# WGPIB.net
KiCad netlist of a schematic drawn in Altium Designer
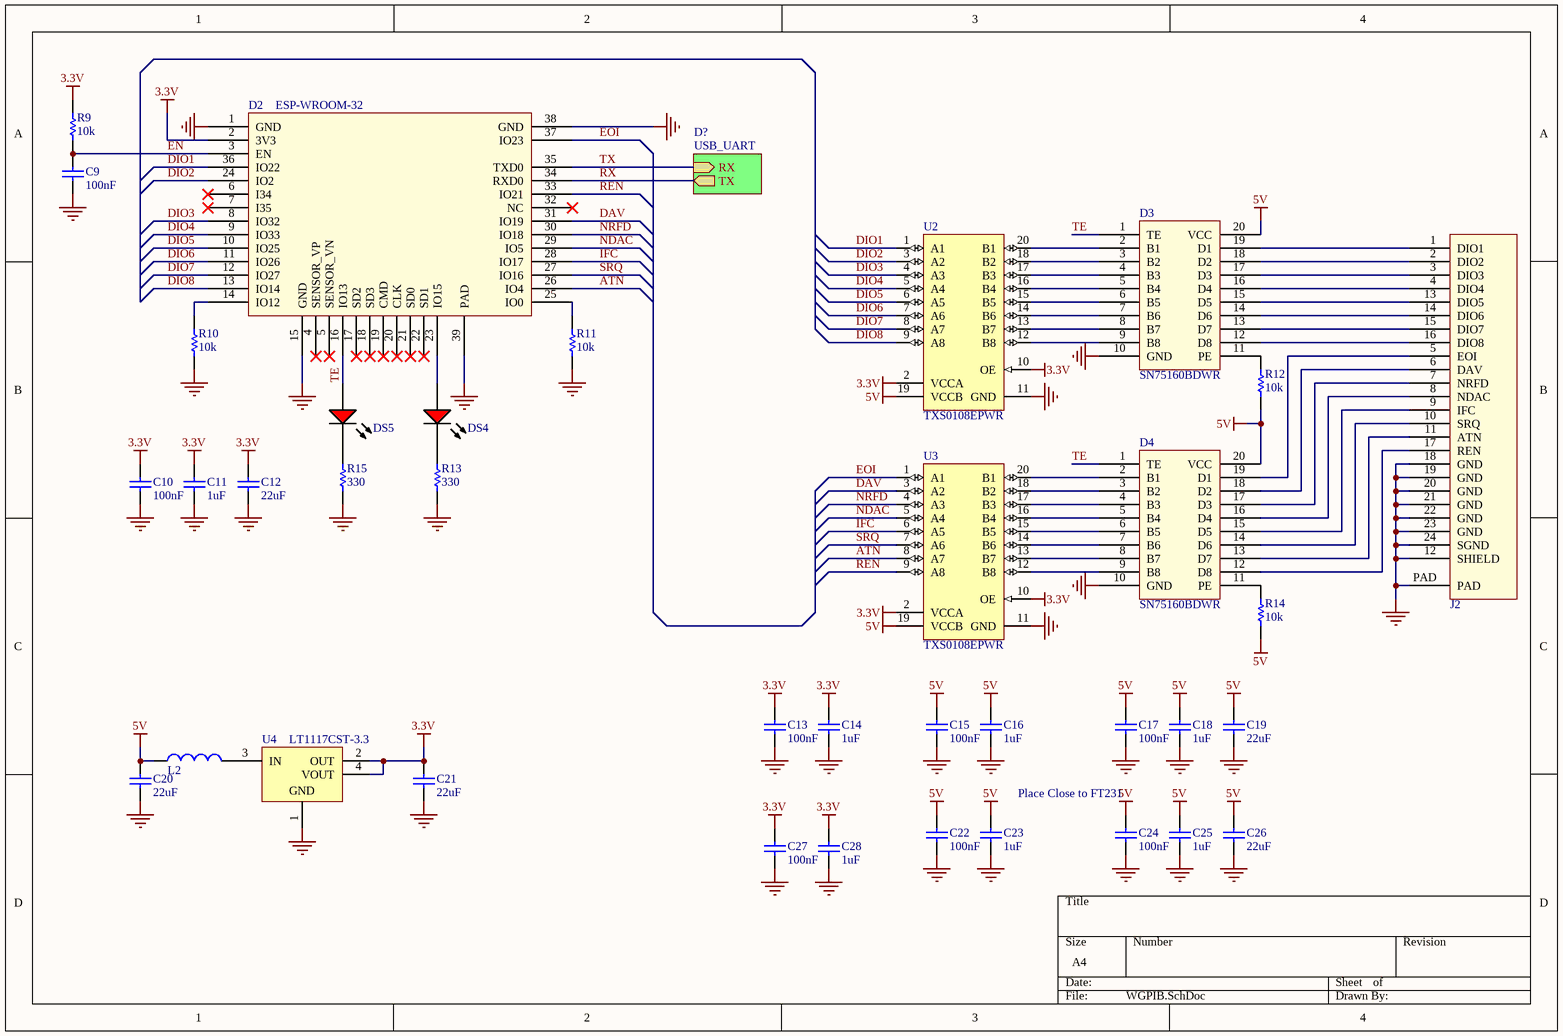
[diagram p0: WGPIB.SchDoc]

(export (version "E")
  (design (tool "Eeschema 10.0.6"))
  (components
    (comp (ref "C9")
      (value "100nF")
      (footprint "CAPC0805(2012)145_N")
      (fields (field (name "TOLERANCE") "Â±20%"))
      (libsource (lib "Altium Content Vault") (part "CAP"))
    )
    (comp (ref "C10")
      (value "100nF")
      (footprint "CAPC0805(2012)145_N")
      (fields (field (name "TOLERANCE") "Â±20%"))
      (libsource (lib "Altium Content Vault") (part "CAP"))
    )
    (comp (ref "C11")
      (value "1uF")
      (footprint "CAPC0805(2012)145_N")
      (fields (field (name "TOLERANCE") "Â±20%"))
      (libsource (lib "Altium Content Vault") (part "CAP"))
    )
    (comp (ref "C12")
      (value "22uF")
      (footprint "CAPC1206(3216)190_M")
      (fields (field (name "TOLERANCE") "Â±20%"))
      (libsource (lib "Altium Content Vault") (part "CAP"))
    )
    (comp (ref "C13")
      (value "100nF")
      (footprint "CAPC0805(2012)145_N")
      (fields (field (name "TOLERANCE") "Â±20%"))
      (libsource (lib "Altium Content Vault") (part "CAP"))
    )
    (comp (ref "C14")
      (value "1uF")
      (footprint "CAPC0805(2012)145_N")
      (fields (field (name "TOLERANCE") "Â±20%"))
      (libsource (lib "Altium Content Vault") (part "CAP"))
    )
    (comp (ref "C15")
      (value "100nF")
      (footprint "CAPC0805(2012)145_N")
      (fields (field (name "TOLERANCE") "Â±20%"))
      (libsource (lib "Altium Content Vault") (part "CAP"))
    )
    (comp (ref "C16")
      (value "1uF")
      (footprint "CAPC0805(2012)145_N")
      (fields (field (name "TOLERANCE") "Â±20%"))
      (libsource (lib "Altium Content Vault") (part "CAP"))
    )
    (comp (ref "C17")
      (value "100nF")
      (footprint "CAPC0805(2012)145_N")
      (fields (field (name "TOLERANCE") "Â±20%"))
      (libsource (lib "Altium Content Vault") (part "CAP"))
    )
    (comp (ref "C18")
      (value "1uF")
      (footprint "CAPC0805(2012)145_N")
      (fields (field (name "TOLERANCE") "Â±20%"))
      (libsource (lib "Altium Content Vault") (part "CAP"))
    )
    (comp (ref "C19")
      (value "22uF")
      (footprint "CAPC1206(3216)190_M")
      (fields (field (name "TOLERANCE") "Â±20%"))
      (libsource (lib "Altium Content Vault") (part "CAP"))
    )
    (comp (ref "C20")
      (value "22uF")
      (footprint "CAPC1206(3216)190_M")
      (fields (field (name "TOLERANCE") "Â±20%"))
      (libsource (lib "Altium Content Vault") (part "CAP"))
    )
    (comp (ref "C21")
      (value "22uF")
      (footprint "CAPC1206(3216)190_M")
      (fields (field (name "TOLERANCE") "Â±20%"))
      (libsource (lib "Altium Content Vault") (part "CAP"))
    )
    (comp (ref "C22")
      (value "100nF")
      (footprint "CAPC0805(2012)145_N")
      (fields (field (name "TOLERANCE") "Â±20%"))
      (libsource (lib "Altium Content Vault") (part "CAP"))
    )
    (comp (ref "C23")
      (value "1uF")
      (footprint "CAPC0805(2012)145_N")
      (fields (field (name "TOLERANCE") "Â±20%"))
      (libsource (lib "Altium Content Vault") (part "CAP"))
    )
    (comp (ref "C24")
      (value "100nF")
      (footprint "CAPC0805(2012)145_N")
      (fields (field (name "TOLERANCE") "Â±20%"))
      (libsource (lib "Altium Content Vault") (part "CAP"))
    )
    (comp (ref "C25")
      (value "1uF")
      (footprint "CAPC0805(2012)145_N")
      (fields (field (name "TOLERANCE") "Â±20%"))
      (libsource (lib "Altium Content Vault") (part "CAP"))
    )
    (comp (ref "C26")
      (value "22uF")
      (footprint "CAPC1206(3216)190_M")
      (fields (field (name "TOLERANCE") "Â±20%"))
      (libsource (lib "Altium Content Vault") (part "CAP"))
    )
    (comp (ref "C27")
      (value "100nF")
      (footprint "CAPC0805(2012)145_N")
      (fields (field (name "TOLERANCE") "Â±20%"))
      (libsource (lib "Altium Content Vault") (part "CAP"))
    )
    (comp (ref "C28")
      (value "1uF")
      (footprint "CAPC0805(2012)145_N")
      (fields (field (name "TOLERANCE") "Â±20%"))
      (libsource (lib "Altium Content Vault") (part "CAP"))
    )
    (comp (ref "D2")
      (value "ESP-WROOM-32")
      (footprint "ESP-WROOM-32")
      (description "ESP32 Module")
      (libsource (lib "DEV_Modules") (part "ESP-WROOM-32"))
    )
    (comp (ref "D3")
      (value "SN75160BDWR")
      (footprint "SOIC-20")
      (libsource (lib "LineDrivers") (part "SN75160BDWR"))
    )
    (comp (ref "D4")
      (value "SN75160BDWR")
      (footprint "SOIC-20")
      (libsource (lib "LineDrivers") (part "SN75160BDWR"))
    )
    (comp (ref "DS4")
      (value "TLMS1100-GS08")
      (footprint "VISH-TLMX1100_V")
      (description "LED, RED, 2.1 V, -40 to 100 degC, 2-Pin SMD (0603), RoHS, Tape and Reel")
      (fields (field (name "TOLERANCE") "5%"))
      (libsource (lib "Altium Content Vault") (part "LED-RED-AK-2"))
    )
    (comp (ref "DS5")
      (value "TLMS1100-GS08")
      (footprint "VISH-TLMX1100_V")
      (description "LED, RED, 2.1 V, -40 to 100 degC, 2-Pin SMD (0603), RoHS, Tape and Reel")
      (fields (field (name "TOLERANCE") "5%"))
      (libsource (lib "Altium Content Vault") (part "LED-RED-AK-2"))
    )
    (comp (ref "J2")
      (value "GPIB")
      (footprint "GPIB THT")
      (description "112-024-113R001")
      (libsource (lib "DSUB_Connector") (part "GPIB"))
    )
    (comp (ref "L2")
      (value "FBMJ2125HM210NT")
      (footprint "INDC2013X105X50LL20T30")
      (description "Chip Inductor, 21 Ohm, +/- 30%, 6 A, -40 to 125 degC, 0805 (2012 Metric), RoHS, Tape and Reel")
      (fields (field (name "TOLERANCE") "30%"))
      (libsource (lib "Altium Content Vault") (part "IND-2"))
    )
    (comp (ref "R9")
      (value "10k")
      (footprint "RESC0805(2012)_M")
      (fields (field (name "POWER") "0.125 W") (field (name "TOLERANCE") "5 %"))
      (libsource (lib "Altium Content Vault") (part "RES"))
    )
    (comp (ref "R10")
      (value "10k")
      (footprint "RESC0805(2012)_M")
      (fields (field (name "POWER") "0.125 W") (field (name "TOLERANCE") "5 %"))
      (libsource (lib "Altium Content Vault") (part "RES"))
    )
    (comp (ref "R11")
      (value "10k")
      (footprint "RESC0805(2012)_M")
      (fields (field (name "POWER") "0.125 W") (field (name "TOLERANCE") "5 %"))
      (libsource (lib "Altium Content Vault") (part "RES"))
    )
    (comp (ref "R12")
      (value "10k")
      (footprint "RESC0805(2012)_M")
      (fields (field (name "POWER") "0.125 W") (field (name "TOLERANCE") "5 %"))
      (libsource (lib "Altium Content Vault") (part "RES"))
    )
    (comp (ref "R13")
      (value "330")
      (footprint "RESC0805(2012)_M")
      (fields (field (name "POWER") "0.125 W") (field (name "TOLERANCE") "5 %"))
      (libsource (lib "Altium Content Vault") (part "RES"))
    )
    (comp (ref "R14")
      (value "10k")
      (footprint "RESC0805(2012)_M")
      (fields (field (name "POWER") "0.125 W") (field (name "TOLERANCE") "5 %"))
      (libsource (lib "Altium Content Vault") (part "RES"))
    )
    (comp (ref "R15")
      (value "330")
      (footprint "RESC0805(2012)_M")
      (fields (field (name "POWER") "0.125 W") (field (name "TOLERANCE") "5 %"))
      (libsource (lib "Altium Content Vault") (part "RES"))
    )
    (comp (ref "U2")
      (value "TXS0108EPWR")
      (footprint "PW0020A_M")
      (fields (field (name "MANUFACTURER") "Texas Instruments"))
      (libsource (lib "Altium Content Vault") (part "TI-TXS0108EPWR-SOP-20"))
    )
    (comp (ref "U3")
      (value "TXS0108EPWR")
      (footprint "PW0020A_M")
      (fields (field (name "MANUFACTURER") "Texas Instruments"))
      (libsource (lib "Altium Content Vault") (part "TI-TXS0108EPWR-SOP-20"))
    )
    (comp (ref "U4")
      (value "LT1117CST-3.3")
      (footprint "LT-ST-3-SOT-223_M")
      (fields (field (name "MANUFACTURER") "Linear Technology"))
      (libsource (lib "Altium Content Vault") (part "LT-LT1117-3_B"))
    )
  )
  (nets
    (net (code "1") (name "/ATN") (class "Default")
      (node (ref "D2") (pin "26") (pinfunction "IO4_26") (pintype "passive"))
      (node (ref "U3") (pin "8") (pinfunction "A7_8") (pintype "bidirectional"))
    )
    (net (code "2") (name "/DAV") (class "Default")
      (node (ref "D2") (pin "31") (pinfunction "IO19_31") (pintype "passive"))
      (node (ref "U3") (pin "3") (pinfunction "A2_3") (pintype "bidirectional"))
    )
    (net (code "3") (name "/DIO1") (class "Default")
      (node (ref "D2") (pin "36") (pinfunction "IO22_36") (pintype "passive"))
      (node (ref "U2") (pin "1") (pinfunction "A1_1") (pintype "bidirectional"))
    )
    (net (code "4") (name "/DIO2") (class "Default")
      (node (ref "D2") (pin "24") (pinfunction "IO2_24") (pintype "passive"))
      (node (ref "U2") (pin "3") (pinfunction "A2_3") (pintype "bidirectional"))
    )
    (net (code "5") (name "/DIO3") (class "Default")
      (node (ref "D2") (pin "8") (pinfunction "IO32_8") (pintype "passive"))
      (node (ref "U2") (pin "4") (pinfunction "A3_4") (pintype "bidirectional"))
    )
    (net (code "6") (name "/DIO4") (class "Default")
      (node (ref "D2") (pin "9") (pinfunction "IO33_9") (pintype "passive"))
      (node (ref "U2") (pin "5") (pinfunction "A4_5") (pintype "bidirectional"))
    )
    (net (code "7") (name "/DIO5") (class "Default")
      (node (ref "D2") (pin "10") (pinfunction "IO25_10") (pintype "passive"))
      (node (ref "U2") (pin "6") (pinfunction "A5_6") (pintype "bidirectional"))
    )
    (net (code "8") (name "/DIO6") (class "Default")
      (node (ref "D2") (pin "11") (pinfunction "IO26_11") (pintype "passive"))
      (node (ref "U2") (pin "7") (pinfunction "A6_7") (pintype "bidirectional"))
    )
    (net (code "9") (name "/DIO7") (class "Default")
      (node (ref "D2") (pin "12") (pinfunction "IO27_12") (pintype "passive"))
      (node (ref "U2") (pin "8") (pinfunction "A7_8") (pintype "bidirectional"))
    )
    (net (code "10") (name "/DIO8") (class "Default")
      (node (ref "D2") (pin "13") (pinfunction "IO14_13") (pintype "passive"))
      (node (ref "U2") (pin "9") (pinfunction "A8_9") (pintype "bidirectional"))
    )
    (net (code "11") (name "/EN") (class "Default")
      (node (ref "C9") (pin "2") (pinfunction "2_2") (pintype "passive"))
      (node (ref "D2") (pin "3") (pinfunction "EN_3") (pintype "passive"))
      (node (ref "R9") (pin "1") (pinfunction "1_1") (pintype "passive"))
    )
    (net (code "12") (name "/EOI") (class "Default")
      (node (ref "D2") (pin "37") (pinfunction "IO23_37") (pintype "passive"))
      (node (ref "U3") (pin "1") (pinfunction "A1_1") (pintype "bidirectional"))
    )
    (net (code "13") (name "/IFC") (class "Default")
      (node (ref "D2") (pin "28") (pinfunction "IO17_28") (pintype "passive"))
      (node (ref "U3") (pin "6") (pinfunction "A5_6") (pintype "bidirectional"))
    )
    (net (code "14") (name "/NDAC") (class "Default")
      (node (ref "D2") (pin "29") (pinfunction "IO5_29") (pintype "passive"))
      (node (ref "U3") (pin "5") (pinfunction "A4_5") (pintype "bidirectional"))
    )
    (net (code "15") (name "/NRFD") (class "Default")
      (node (ref "D2") (pin "30") (pinfunction "IO18_30") (pintype "passive"))
      (node (ref "U3") (pin "4") (pinfunction "A3_4") (pintype "bidirectional"))
    )
    (net (code "16") (name "/REN") (class "Default")
      (node (ref "D2") (pin "33") (pinfunction "IO21_33") (pintype "passive"))
      (node (ref "U3") (pin "9") (pinfunction "A8_9") (pintype "bidirectional"))
    )
    (net (code "17") (name "/RX") (class "Default")
      (node (ref "D2") (pin "34") (pinfunction "RXD0_34") (pintype "passive"))
    )
    (net (code "18") (name "/SRQ") (class "Default")
      (node (ref "D2") (pin "27") (pinfunction "IO16_27") (pintype "passive"))
      (node (ref "U3") (pin "7") (pinfunction "A6_7") (pintype "bidirectional"))
    )
    (net (code "19") (name "/TE") (class "Default")
      (node (ref "D2") (pin "16") (pinfunction "IO13_16") (pintype "passive"))
      (node (ref "D3") (pin "1") (pinfunction "TE_1") (pintype "passive"))
      (node (ref "D4") (pin "1") (pinfunction "TE_1") (pintype "passive"))
      (node (ref "DS5") (pin "1") (pinfunction "A_1") (pintype "passive"))
    )
    (net (code "20") (name "/TX") (class "Default")
      (node (ref "D2") (pin "35") (pinfunction "TXD0_35") (pintype "passive"))
    )
    (net (code "21") (name "3.3V") (class "Default")
      (node (ref "C10") (pin "2") (pinfunction "2_2") (pintype "passive"))
      (node (ref "C11") (pin "2") (pinfunction "2_2") (pintype "passive"))
      (node (ref "C12") (pin "2") (pinfunction "2_2") (pintype "passive"))
      (node (ref "C13") (pin "2") (pinfunction "2_2") (pintype "passive"))
      (node (ref "C14") (pin "2") (pinfunction "2_2") (pintype "passive"))
      (node (ref "C21") (pin "2") (pinfunction "2_2") (pintype "passive"))
      (node (ref "C27") (pin "2") (pinfunction "2_2") (pintype "passive"))
      (node (ref "C28") (pin "2") (pinfunction "2_2") (pintype "passive"))
      (node (ref "D2") (pin "2") (pinfunction "3V3_2") (pintype "passive"))
      (node (ref "R9") (pin "2") (pinfunction "2_2") (pintype "passive"))
      (node (ref "U2") (pin "10") (pinfunction "OE_10") (pintype "input"))
      (node (ref "U2") (pin "2") (pinfunction "VCCA_2") (pintype "power_in"))
      (node (ref "U3") (pin "10") (pinfunction "OE_10") (pintype "input"))
      (node (ref "U3") (pin "2") (pinfunction "VCCA_2") (pintype "power_in"))
      (node (ref "U4") (pin "2") (pinfunction "OUT_2") (pintype "power_in"))
      (node (ref "U4") (pin "4") (pinfunction "VOUT_4") (pintype "power_in"))
    )
    (net (code "22") (name "5V") (class "Default")
      (node (ref "C15") (pin "2") (pinfunction "2_2") (pintype "passive"))
      (node (ref "C16") (pin "2") (pinfunction "2_2") (pintype "passive"))
      (node (ref "C17") (pin "2") (pinfunction "2_2") (pintype "passive"))
      (node (ref "C18") (pin "2") (pinfunction "2_2") (pintype "passive"))
      (node (ref "C19") (pin "2") (pinfunction "2_2") (pintype "passive"))
      (node (ref "C20") (pin "2") (pinfunction "2_2") (pintype "passive"))
      (node (ref "C22") (pin "2") (pinfunction "2_2") (pintype "passive"))
      (node (ref "C23") (pin "2") (pinfunction "2_2") (pintype "passive"))
      (node (ref "C24") (pin "2") (pinfunction "2_2") (pintype "passive"))
      (node (ref "C25") (pin "2") (pinfunction "2_2") (pintype "passive"))
      (node (ref "C26") (pin "2") (pinfunction "2_2") (pintype "passive"))
      (node (ref "D3") (pin "20") (pinfunction "VCC_20") (pintype "passive"))
      (node (ref "D4") (pin "20") (pinfunction "VCC_20") (pintype "passive"))
      (node (ref "L2") (pin "1") (pinfunction "1_1") (pintype "passive"))
      (node (ref "R12") (pin "1") (pinfunction "1_1") (pintype "passive"))
      (node (ref "R14") (pin "1") (pinfunction "1_1") (pintype "passive"))
      (node (ref "U2") (pin "19") (pinfunction "VCCB_19") (pintype "power_in"))
      (node (ref "U3") (pin "19") (pinfunction "VCCB_19") (pintype "power_in"))
    )
    (net (code "23") (name "GND") (class "Default")
      (node (ref "C10") (pin "1") (pinfunction "1_1") (pintype "passive"))
      (node (ref "C11") (pin "1") (pinfunction "1_1") (pintype "passive"))
      (node (ref "C12") (pin "1") (pinfunction "1_1") (pintype "passive"))
      (node (ref "C13") (pin "1") (pinfunction "1_1") (pintype "passive"))
      (node (ref "C14") (pin "1") (pinfunction "1_1") (pintype "passive"))
      (node (ref "C15") (pin "1") (pinfunction "1_1") (pintype "passive"))
      (node (ref "C16") (pin "1") (pinfunction "1_1") (pintype "passive"))
      (node (ref "C17") (pin "1") (pinfunction "1_1") (pintype "passive"))
      (node (ref "C18") (pin "1") (pinfunction "1_1") (pintype "passive"))
      (node (ref "C19") (pin "1") (pinfunction "1_1") (pintype "passive"))
      (node (ref "C20") (pin "1") (pinfunction "1_1") (pintype "passive"))
      (node (ref "C21") (pin "1") (pinfunction "1_1") (pintype "passive"))
      (node (ref "C22") (pin "1") (pinfunction "1_1") (pintype "passive"))
      (node (ref "C23") (pin "1") (pinfunction "1_1") (pintype "passive"))
      (node (ref "C24") (pin "1") (pinfunction "1_1") (pintype "passive"))
      (node (ref "C25") (pin "1") (pinfunction "1_1") (pintype "passive"))
      (node (ref "C26") (pin "1") (pinfunction "1_1") (pintype "passive"))
      (node (ref "C27") (pin "1") (pinfunction "1_1") (pintype "passive"))
      (node (ref "C28") (pin "1") (pinfunction "1_1") (pintype "passive"))
      (node (ref "C9") (pin "1") (pinfunction "1_1") (pintype "passive"))
      (node (ref "D2") (pin "1") (pinfunction "GND_1") (pintype "passive"))
      (node (ref "D2") (pin "15") (pinfunction "GND_15") (pintype "passive"))
      (node (ref "D2") (pin "38") (pinfunction "GND_38") (pintype "passive"))
      (node (ref "D2") (pin "39") (pinfunction "PAD_39") (pintype "passive"))
      (node (ref "D3") (pin "10") (pinfunction "GND_10") (pintype "passive"))
      (node (ref "D4") (pin "10") (pinfunction "GND_10") (pintype "passive"))
      (node (ref "J2") (pin "12") (pinfunction "SHIELD_12") (pintype "passive"))
      (node (ref "J2") (pin "18") (pinfunction "GND_18") (pintype "passive"))
      (node (ref "J2") (pin "19") (pinfunction "GND_19") (pintype "passive"))
      (node (ref "J2") (pin "20") (pinfunction "GND_20") (pintype "passive"))
      (node (ref "J2") (pin "21") (pinfunction "GND_21") (pintype "passive"))
      (node (ref "J2") (pin "22") (pinfunction "GND_22") (pintype "passive"))
      (node (ref "J2") (pin "23") (pinfunction "GND_23") (pintype "passive"))
      (node (ref "J2") (pin "24") (pinfunction "SGND_24") (pintype "passive"))
      (node (ref "J2") (pin "PAD") (pinfunction "PAD_PAD") (pintype "passive"))
      (node (ref "R10") (pin "1") (pinfunction "1_1") (pintype "passive"))
      (node (ref "R11") (pin "1") (pinfunction "1_1") (pintype "passive"))
      (node (ref "R13") (pin "1") (pinfunction "1_1") (pintype "passive"))
      (node (ref "R15") (pin "1") (pinfunction "1_1") (pintype "passive"))
      (node (ref "U2") (pin "11") (pinfunction "GND_11") (pintype "power_in"))
      (node (ref "U3") (pin "11") (pinfunction "GND_11") (pintype "power_in"))
      (node (ref "U4") (pin "1") (pinfunction "GND_1") (pintype "power_in"))
    )
    (net (code "24") (name "Net-(D2-IO0)") (class "Default")
      (node (ref "D2") (pin "25") (pinfunction "IO0_25") (pintype "passive"))
      (node (ref "R11") (pin "2") (pinfunction "2_2") (pintype "passive"))
    )
    (net (code "25") (name "Net-(D2-IO12)") (class "Default")
      (node (ref "D2") (pin "14") (pinfunction "IO12_14") (pintype "passive"))
      (node (ref "R10") (pin "2") (pinfunction "2_2") (pintype "passive"))
    )
    (net (code "26") (name "Net-(D2-IO15)") (class "Default")
      (node (ref "D2") (pin "23") (pinfunction "IO15_23") (pintype "passive"))
      (node (ref "DS4") (pin "1") (pinfunction "A_1") (pintype "passive"))
    )
    (net (code "27") (name "Net-(D3-B1)") (class "Default")
      (node (ref "D3") (pin "2") (pinfunction "B1_2") (pintype "passive"))
      (node (ref "U2") (pin "20") (pinfunction "B1_20") (pintype "bidirectional"))
    )
    (net (code "28") (name "Net-(D3-B2)") (class "Default")
      (node (ref "D3") (pin "3") (pinfunction "B2_3") (pintype "passive"))
      (node (ref "U2") (pin "18") (pinfunction "B2_18") (pintype "bidirectional"))
    )
    (net (code "29") (name "Net-(D3-B3)") (class "Default")
      (node (ref "D3") (pin "4") (pinfunction "B3_4") (pintype "passive"))
      (node (ref "U2") (pin "17") (pinfunction "B3_17") (pintype "bidirectional"))
    )
    (net (code "30") (name "Net-(D3-B4)") (class "Default")
      (node (ref "D3") (pin "5") (pinfunction "B4_5") (pintype "passive"))
      (node (ref "U2") (pin "16") (pinfunction "B4_16") (pintype "bidirectional"))
    )
    (net (code "31") (name "Net-(D3-B5)") (class "Default")
      (node (ref "D3") (pin "6") (pinfunction "B5_6") (pintype "passive"))
      (node (ref "U2") (pin "15") (pinfunction "B5_15") (pintype "bidirectional"))
    )
    (net (code "32") (name "Net-(D3-B6)") (class "Default")
      (node (ref "D3") (pin "7") (pinfunction "B6_7") (pintype "passive"))
      (node (ref "U2") (pin "14") (pinfunction "B6_14") (pintype "bidirectional"))
    )
    (net (code "33") (name "Net-(D3-B7)") (class "Default")
      (node (ref "D3") (pin "8") (pinfunction "B7_8") (pintype "passive"))
      (node (ref "U2") (pin "13") (pinfunction "B7_13") (pintype "bidirectional"))
    )
    (net (code "34") (name "Net-(D3-B8)") (class "Default")
      (node (ref "D3") (pin "9") (pinfunction "B8_9") (pintype "passive"))
      (node (ref "U2") (pin "12") (pinfunction "B8_12") (pintype "bidirectional"))
    )
    (net (code "35") (name "Net-(D3-D1)") (class "Default")
      (node (ref "D3") (pin "19") (pinfunction "D1_19") (pintype "passive"))
      (node (ref "J2") (pin "1") (pinfunction "DIO1_1") (pintype "passive"))
    )
    (net (code "36") (name "Net-(D3-D2)") (class "Default")
      (node (ref "D3") (pin "18") (pinfunction "D2_18") (pintype "passive"))
      (node (ref "J2") (pin "2") (pinfunction "DIO2_2") (pintype "passive"))
    )
    (net (code "37") (name "Net-(D3-D3)") (class "Default")
      (node (ref "D3") (pin "17") (pinfunction "D3_17") (pintype "passive"))
      (node (ref "J2") (pin "3") (pinfunction "DIO3_3") (pintype "passive"))
    )
    (net (code "38") (name "Net-(D3-D4)") (class "Default")
      (node (ref "D3") (pin "16") (pinfunction "D4_16") (pintype "passive"))
      (node (ref "J2") (pin "4") (pinfunction "DIO4_4") (pintype "passive"))
    )
    (net (code "39") (name "Net-(D3-D5)") (class "Default")
      (node (ref "D3") (pin "15") (pinfunction "D5_15") (pintype "passive"))
      (node (ref "J2") (pin "13") (pinfunction "DIO5_13") (pintype "passive"))
    )
    (net (code "40") (name "Net-(D3-D6)") (class "Default")
      (node (ref "D3") (pin "14") (pinfunction "D6_14") (pintype "passive"))
      (node (ref "J2") (pin "14") (pinfunction "DIO6_14") (pintype "passive"))
    )
    (net (code "41") (name "Net-(D3-D7)") (class "Default")
      (node (ref "D3") (pin "13") (pinfunction "D7_13") (pintype "passive"))
      (node (ref "J2") (pin "15") (pinfunction "DIO7_15") (pintype "passive"))
    )
    (net (code "42") (name "Net-(D3-D8)") (class "Default")
      (node (ref "D3") (pin "12") (pinfunction "D8_12") (pintype "passive"))
      (node (ref "J2") (pin "16") (pinfunction "DIO8_16") (pintype "passive"))
    )
    (net (code "43") (name "Net-(D3-PE)") (class "Default")
      (node (ref "D3") (pin "11") (pinfunction "PE_11") (pintype "passive"))
      (node (ref "R12") (pin "2") (pinfunction "2_2") (pintype "passive"))
    )
    (net (code "44") (name "Net-(D4-B1)") (class "Default")
      (node (ref "D4") (pin "2") (pinfunction "B1_2") (pintype "passive"))
      (node (ref "U3") (pin "20") (pinfunction "B1_20") (pintype "bidirectional"))
    )
    (net (code "45") (name "Net-(D4-B2)") (class "Default")
      (node (ref "D4") (pin "3") (pinfunction "B2_3") (pintype "passive"))
      (node (ref "U3") (pin "18") (pinfunction "B2_18") (pintype "bidirectional"))
    )
    (net (code "46") (name "Net-(D4-B3)") (class "Default")
      (node (ref "D4") (pin "4") (pinfunction "B3_4") (pintype "passive"))
      (node (ref "U3") (pin "17") (pinfunction "B3_17") (pintype "bidirectional"))
    )
    (net (code "47") (name "Net-(D4-B4)") (class "Default")
      (node (ref "D4") (pin "5") (pinfunction "B4_5") (pintype "passive"))
      (node (ref "U3") (pin "16") (pinfunction "B4_16") (pintype "bidirectional"))
    )
    (net (code "48") (name "Net-(D4-B5)") (class "Default")
      (node (ref "D4") (pin "6") (pinfunction "B5_6") (pintype "passive"))
      (node (ref "U3") (pin "15") (pinfunction "B5_15") (pintype "bidirectional"))
    )
    (net (code "49") (name "Net-(D4-B6)") (class "Default")
      (node (ref "D4") (pin "7") (pinfunction "B6_7") (pintype "passive"))
      (node (ref "U3") (pin "14") (pinfunction "B6_14") (pintype "bidirectional"))
    )
    (net (code "50") (name "Net-(D4-B7)") (class "Default")
      (node (ref "D4") (pin "8") (pinfunction "B7_8") (pintype "passive"))
      (node (ref "U3") (pin "13") (pinfunction "B7_13") (pintype "bidirectional"))
    )
    (net (code "51") (name "Net-(D4-B8)") (class "Default")
      (node (ref "D4") (pin "9") (pinfunction "B8_9") (pintype "passive"))
      (node (ref "U3") (pin "12") (pinfunction "B8_12") (pintype "bidirectional"))
    )
    (net (code "52") (name "Net-(D4-D1)") (class "Default")
      (node (ref "D4") (pin "19") (pinfunction "D1_19") (pintype "passive"))
      (node (ref "J2") (pin "5") (pinfunction "EOI_5") (pintype "passive"))
    )
    (net (code "53") (name "Net-(D4-D2)") (class "Default")
      (node (ref "D4") (pin "18") (pinfunction "D2_18") (pintype "passive"))
      (node (ref "J2") (pin "6") (pinfunction "DAV_6") (pintype "passive"))
    )
    (net (code "54") (name "Net-(D4-D3)") (class "Default")
      (node (ref "D4") (pin "17") (pinfunction "D3_17") (pintype "passive"))
      (node (ref "J2") (pin "7") (pinfunction "NRFD_7") (pintype "passive"))
    )
    (net (code "55") (name "Net-(D4-D4)") (class "Default")
      (node (ref "D4") (pin "16") (pinfunction "D4_16") (pintype "passive"))
      (node (ref "J2") (pin "8") (pinfunction "NDAC_8") (pintype "passive"))
    )
    (net (code "56") (name "Net-(D4-D5)") (class "Default")
      (node (ref "D4") (pin "15") (pinfunction "D5_15") (pintype "passive"))
      (node (ref "J2") (pin "9") (pinfunction "IFC_9") (pintype "passive"))
    )
    (net (code "57") (name "Net-(D4-D6)") (class "Default")
      (node (ref "D4") (pin "14") (pinfunction "D6_14") (pintype "passive"))
      (node (ref "J2") (pin "10") (pinfunction "SRQ_10") (pintype "passive"))
    )
    (net (code "58") (name "Net-(D4-D7)") (class "Default")
      (node (ref "D4") (pin "13") (pinfunction "D7_13") (pintype "passive"))
      (node (ref "J2") (pin "11") (pinfunction "ATN_11") (pintype "passive"))
    )
    (net (code "59") (name "Net-(D4-D8)") (class "Default")
      (node (ref "D4") (pin "12") (pinfunction "D8_12") (pintype "passive"))
      (node (ref "J2") (pin "17") (pinfunction "REN_17") (pintype "passive"))
    )
    (net (code "60") (name "Net-(D4-PE)") (class "Default")
      (node (ref "D4") (pin "11") (pinfunction "PE_11") (pintype "passive"))
      (node (ref "R14") (pin "2") (pinfunction "2_2") (pintype "passive"))
    )
    (net (code "61") (name "Net-(DS4-K)") (class "Default")
      (node (ref "DS4") (pin "2") (pinfunction "K_2") (pintype "passive"))
      (node (ref "R13") (pin "2") (pinfunction "2_2") (pintype "passive"))
    )
    (net (code "62") (name "Net-(DS5-K)") (class "Default")
      (node (ref "DS5") (pin "2") (pinfunction "K_2") (pintype "passive"))
      (node (ref "R15") (pin "2") (pinfunction "2_2") (pintype "passive"))
    )
    (net (code "63") (name "Net-(U4-IN)") (class "Default")
      (node (ref "L2") (pin "2") (pinfunction "2_2") (pintype "passive"))
      (node (ref "U4") (pin "3") (pinfunction "IN_3") (pintype "power_in"))
    )
    (net (code "64") (name "unconnected-(D2-CLK-Pad20)") (class "Default")
      (node (ref "D2") (pin "20") (pinfunction "CLK_20") (pintype "passive+no_connect"))
    )
    (net (code "65") (name "unconnected-(D2-CMD-Pad19)") (class "Default")
      (node (ref "D2") (pin "19") (pinfunction "CMD_19") (pintype "passive+no_connect"))
    )
    (net (code "66") (name "unconnected-(D2-I34-Pad6)") (class "Default")
      (node (ref "D2") (pin "6") (pinfunction "I34_6") (pintype "passive+no_connect"))
    )
    (net (code "67") (name "unconnected-(D2-I35-Pad7)") (class "Default")
      (node (ref "D2") (pin "7") (pinfunction "I35_7") (pintype "passive+no_connect"))
    )
    (net (code "68") (name "unconnected-(D2-NC-Pad32)") (class "Default")
      (node (ref "D2") (pin "32") (pinfunction "NC_32") (pintype "passive+no_connect"))
    )
    (net (code "69") (name "unconnected-(D2-SD0-Pad21)") (class "Default")
      (node (ref "D2") (pin "21") (pinfunction "SD0_21") (pintype "passive+no_connect"))
    )
    (net (code "70") (name "unconnected-(D2-SD1-Pad22)") (class "Default")
      (node (ref "D2") (pin "22") (pinfunction "SD1_22") (pintype "passive+no_connect"))
    )
    (net (code "71") (name "unconnected-(D2-SD2-Pad17)") (class "Default")
      (node (ref "D2") (pin "17") (pinfunction "SD2_17") (pintype "passive+no_connect"))
    )
    (net (code "72") (name "unconnected-(D2-SD3-Pad18)") (class "Default")
      (node (ref "D2") (pin "18") (pinfunction "SD3_18") (pintype "passive+no_connect"))
    )
    (net (code "73") (name "unconnected-(D2-SENSOR_VN-Pad5)") (class "Default")
      (node (ref "D2") (pin "5") (pinfunction "SENSOR_VN_5") (pintype "passive+no_connect"))
    )
    (net (code "74") (name "unconnected-(D2-SENSOR_VP-Pad4)") (class "Default")
      (node (ref "D2") (pin "4") (pinfunction "SENSOR_VP_4") (pintype "passive+no_connect"))
    )
  )
)
